# feederboard.net
KiCad netlist of a schematic drawn in EAGLE
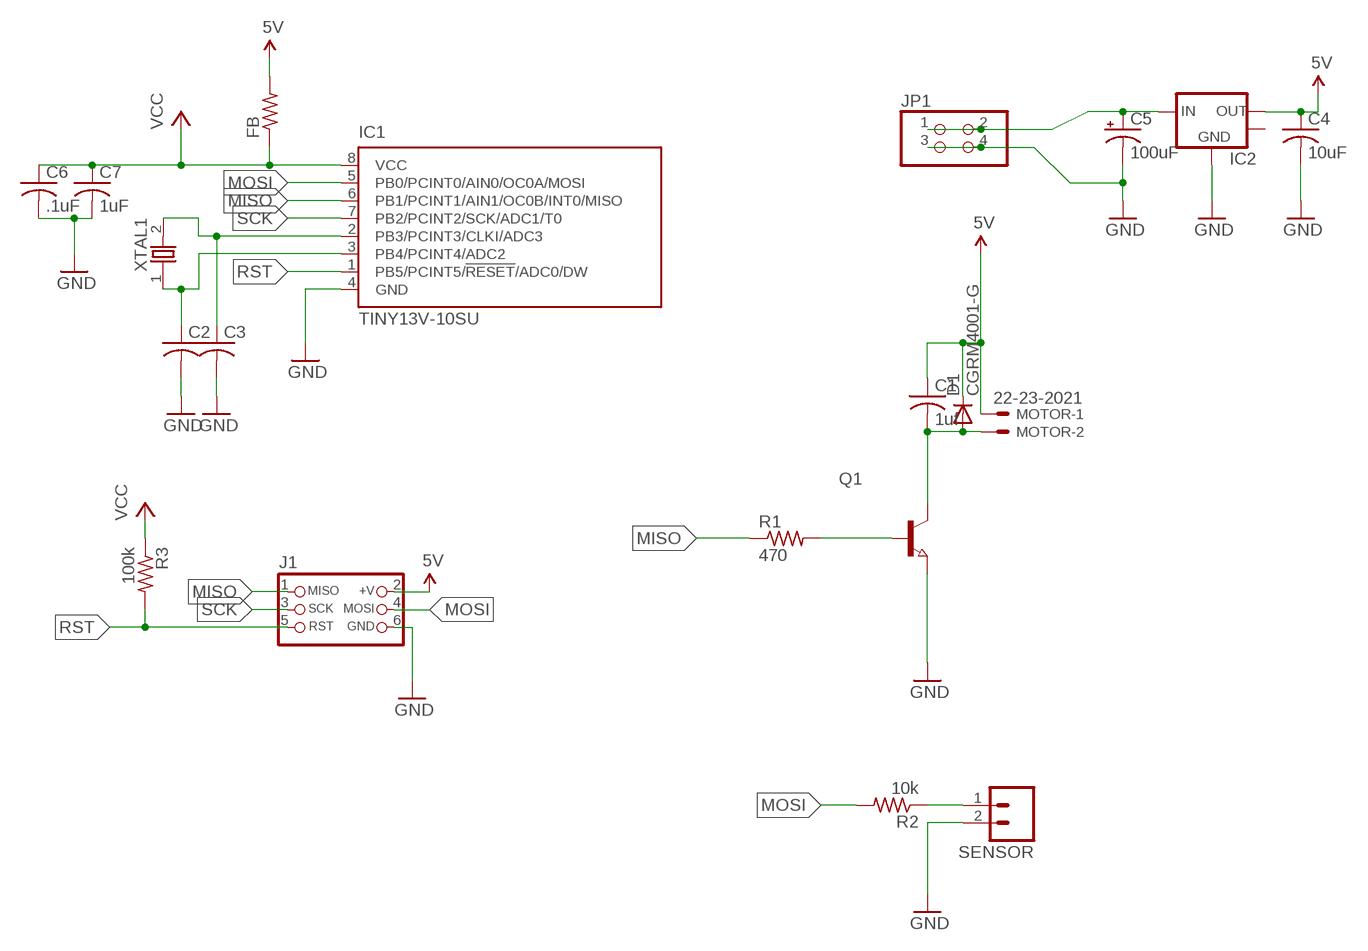
[diagram p0: schematic, sheet 1]

(export (version "E")
  (design (tool "Eeschema 10.0.6"))
  (components
    (comp (ref "C1")
      (value "1uf")
      (footprint "eagle-import:C0805K")
      (libsource (lib "eagle-import") (part "C-USC0805K"))
    )
    (comp (ref "C2")
      (value "C-USC0805")
      (footprint "eagle-import:C0805")
      (libsource (lib "eagle-import") (part "C-USC0805"))
    )
    (comp (ref "C3")
      (value "C-USC0805")
      (footprint "eagle-import:C0805")
      (libsource (lib "eagle-import") (part "C-USC0805"))
    )
    (comp (ref "C4")
      (value "10uF")
      (footprint "eagle-import:C0805K")
      (libsource (lib "eagle-import") (part "C-USC0805K"))
    )
    (comp (ref "C5")
      (value "100uF")
      (footprint "eagle-import:PANASONIC_C")
      (libsource (lib "eagle-import") (part "CPOL-USC"))
    )
    (comp (ref "C6")
      (value ".1uF")
      (footprint "eagle-import:C0603")
      (libsource (lib "eagle-import") (part "C-USC0603"))
    )
    (comp (ref "C7")
      (value "1uF")
      (footprint "eagle-import:C0603")
      (libsource (lib "eagle-import") (part "C-USC0603"))
    )
    (comp (ref "D1")
      (value "CGRM4001-G")
      (footprint "eagle-import:SOD-123_MINI-SMA")
      (libsource (lib "eagle-import") (part "CGRM400-G1"))
    )
    (comp (ref "FB")
      (value "R-US_R0805")
      (footprint "eagle-import:R0805")
      (libsource (lib "eagle-import") (part "R-US_R0805"))
    )
    (comp (ref "IC1")
      (value "TINY13V-10SU")
      (footprint "eagle-import:8S2")
      (fields (field (name "MPN") "ATTINY13V-10SU"))
      (libsource (lib "eagle-import") (part "TINY13SUV-10"))
    )
    (comp (ref "IC2")
      (value "V_REG_LM1117SOT223")
      (footprint "eagle-import:SOT223")
      (libsource (lib "eagle-import") (part "V_REG_LM1117SOT223"))
    )
    (comp (ref "J1")
      (value "CON_HEADER_PRG_AVR_ICSP_ETCH")
      (footprint "eagle-import:HEADER_PRG_2X03_ETCH")
      (libsource (lib "eagle-import") (part "CON_HEADER_PRG_AVR_ICSP_ETCH"))
    )
    (comp (ref "JP1")
      (value "PINHD-2X2/90")
      (footprint "eagle-import:2X02_90")
      (libsource (lib "eagle-import") (part "PINHD-2X2/90"))
    )
    (comp (ref "MOTOR")
      (value "22-23-2021")
      (footprint "eagle-import:22-23-2021")
      (fields (field (name "MF") "MOLEX"))
      (libsource (lib "eagle-import") (part "22-23-2021"))
    )
    (comp (ref "Q1")
      (value "NPN-TRANSISTOR_SOT23")
      (footprint "eagle-import:SOT23")
      (libsource (lib "eagle-import") (part "NPN-TRANSISTOR_SOT23"))
    )
    (comp (ref "R1")
      (value "470")
      (footprint "eagle-import:R0805")
      (libsource (lib "eagle-import") (part "R-US_R0805"))
    )
    (comp (ref "R2")
      (value "10k")
      (footprint "eagle-import:R0805")
      (libsource (lib "eagle-import") (part "R-US_R0805"))
    )
    (comp (ref "R3")
      (value "100k")
      (footprint "eagle-import:R0805")
      (libsource (lib "eagle-import") (part "R-US_R0805"))
    )
    (comp (ref "SENSOR")
      (value "M02JST-PTH-2")
      (footprint "eagle-import:JST-2-PTH")
      (libsource (lib "eagle-import") (part "M02JST-PTH-2"))
    )
    (comp (ref "XTAL1")
      (value "OSC-XTAL")
      (footprint "eagle-import:HC-49U-OR-DIP")
      (libsource (lib "eagle-import") (part "OSC-XTAL"))
    )
  )
  (nets
    (net (code "1") (name "/OUT") (class "Default")
      (node (ref "IC2") (pin "4") (pinfunction "OUT_4") (pintype "power_in"))
    )
    (net (code "2") (name "5V") (class "Default")
      (node (ref "C1") (pin "1") (pinfunction "1_1") (pintype "passive"))
      (node (ref "C4") (pin "1") (pinfunction "1_1") (pintype "passive"))
      (node (ref "D1") (pin "C") (pinfunction "C_C") (pintype "passive"))
      (node (ref "FB") (pin "2") (pinfunction "2_2") (pintype "passive"))
      (node (ref "IC2") (pin "2") (pinfunction "VR-OUTSM_2") (pintype "power_in"))
      (node (ref "J1") (pin "2") (pinfunction "+V_2") (pintype "passive"))
      (node (ref "MOTOR") (pin "1") (pinfunction "S_1") (pintype "passive"))
    )
    (net (code "3") (name "GND") (class "Default")
      (node (ref "C2") (pin "2") (pinfunction "2_2") (pintype "passive"))
      (node (ref "C3") (pin "2") (pinfunction "2_2") (pintype "passive"))
      (node (ref "C4") (pin "2") (pinfunction "2_2") (pintype "passive"))
      (node (ref "C5") (pin "-") (pinfunction "-_-") (pintype "passive"))
      (node (ref "C6") (pin "2") (pinfunction "2_2") (pintype "passive"))
      (node (ref "C7") (pin "2") (pinfunction "2_2") (pintype "passive"))
      (node (ref "IC1") (pin "4") (pinfunction "GND_4") (pintype "power_in"))
      (node (ref "IC2") (pin "1") (pinfunction "GND_1") (pintype "input"))
      (node (ref "J1") (pin "6") (pinfunction "GND_6") (pintype "passive"))
      (node (ref "JP1") (pin "3") (pinfunction "3_3") (pintype "passive"))
      (node (ref "JP1") (pin "4") (pinfunction "4_4") (pintype "passive"))
      (node (ref "Q1") (pin "2") (pinfunction "E_2") (pintype "passive"))
      (node (ref "SENSOR") (pin "2") (pinfunction "2_2") (pintype "passive"))
    )
    (net (code "4") (name "MISO") (class "Default")
      (node (ref "IC1") (pin "6") (pinfunction "PB1/PCINT1/AIN1/OC0B/INT0/MISO_6") (pintype "bidirectional"))
      (node (ref "J1") (pin "1") (pinfunction "MISO_1") (pintype "passive"))
      (node (ref "R1") (pin "1") (pinfunction "1_1") (pintype "passive"))
    )
    (net (code "5") (name "MOSI") (class "Default")
      (node (ref "IC1") (pin "5") (pinfunction "PB0/PCINT0/AIN0/OC0A/MOSI_5") (pintype "bidirectional"))
      (node (ref "J1") (pin "4") (pinfunction "MOSI_4") (pintype "passive"))
      (node (ref "R2") (pin "2") (pinfunction "2_2") (pintype "passive"))
    )
    (net (code "6") (name "Net-(IC1-PB3{slash}PCINT3{slash}CLKI{slash}ADC3)") (class "Default")
      (node (ref "C3") (pin "1") (pinfunction "1_1") (pintype "passive"))
      (node (ref "IC1") (pin "2") (pinfunction "PB3/PCINT3/CLKI/ADC3_2") (pintype "bidirectional"))
      (node (ref "XTAL1") (pin "2") (pinfunction "2_2") (pintype "passive"))
    )
    (net (code "7") (name "Net-(IC1-PB4{slash}PCINT4{slash}ADC2)") (class "Default")
      (node (ref "C2") (pin "1") (pinfunction "1_1") (pintype "passive"))
      (node (ref "IC1") (pin "3") (pinfunction "PB4/PCINT4/ADC2_3") (pintype "bidirectional"))
      (node (ref "XTAL1") (pin "1") (pinfunction "1_1") (pintype "passive"))
    )
    (net (code "8") (name "Net-(IC2-IN)") (class "Default")
      (node (ref "C5") (pin "+") (pinfunction "+_+") (pintype "passive"))
      (node (ref "IC2") (pin "3") (pinfunction "IN_3") (pintype "input"))
      (node (ref "JP1") (pin "1") (pinfunction "1_1") (pintype "passive"))
      (node (ref "JP1") (pin "2") (pinfunction "2_2") (pintype "passive"))
    )
    (net (code "9") (name "Net-(MOTORB-S)") (class "Default")
      (node (ref "C1") (pin "2") (pinfunction "2_2") (pintype "passive"))
      (node (ref "D1") (pin "A") (pinfunction "A_A") (pintype "passive"))
      (node (ref "MOTOR") (pin "2") (pinfunction "S_2") (pintype "passive"))
      (node (ref "Q1") (pin "3") (pinfunction "C_3") (pintype "passive"))
    )
    (net (code "10") (name "Net-(Q1-B)") (class "Default")
      (node (ref "Q1") (pin "1") (pinfunction "B_1") (pintype "passive"))
      (node (ref "R1") (pin "2") (pinfunction "2_2") (pintype "passive"))
    )
    (net (code "11") (name "Net-(R2-Pad1)") (class "Default")
      (node (ref "R2") (pin "1") (pinfunction "1_1") (pintype "passive"))
      (node (ref "SENSOR") (pin "1") (pinfunction "1_1") (pintype "passive"))
    )
    (net (code "12") (name "RST") (class "Default")
      (node (ref "IC1") (pin "1") (pinfunction "PB5/PCINT5/~{RESET}/ADC0/DW_1") (pintype "bidirectional"))
      (node (ref "J1") (pin "5") (pinfunction "RST_5") (pintype "passive"))
      (node (ref "R3") (pin "2") (pinfunction "2_2") (pintype "passive"))
    )
    (net (code "13") (name "SCK") (class "Default")
      (node (ref "IC1") (pin "7") (pinfunction "PB2/PCINT2/SCK/ADC1/T0_7") (pintype "bidirectional"))
      (node (ref "J1") (pin "3") (pinfunction "SCK_3") (pintype "passive"))
    )
    (net (code "14") (name "VCC") (class "Default")
      (node (ref "C6") (pin "1") (pinfunction "1_1") (pintype "passive"))
      (node (ref "C7") (pin "1") (pinfunction "1_1") (pintype "passive"))
      (node (ref "FB") (pin "1") (pinfunction "1_1") (pintype "passive"))
      (node (ref "IC1") (pin "8") (pinfunction "VCC_8") (pintype "power_in"))
      (node (ref "R3") (pin "1") (pinfunction "1_1") (pintype "passive"))
    )
  )
)
